# Screen.net
KiCad netlist of a schematic drawn in Altium Designer
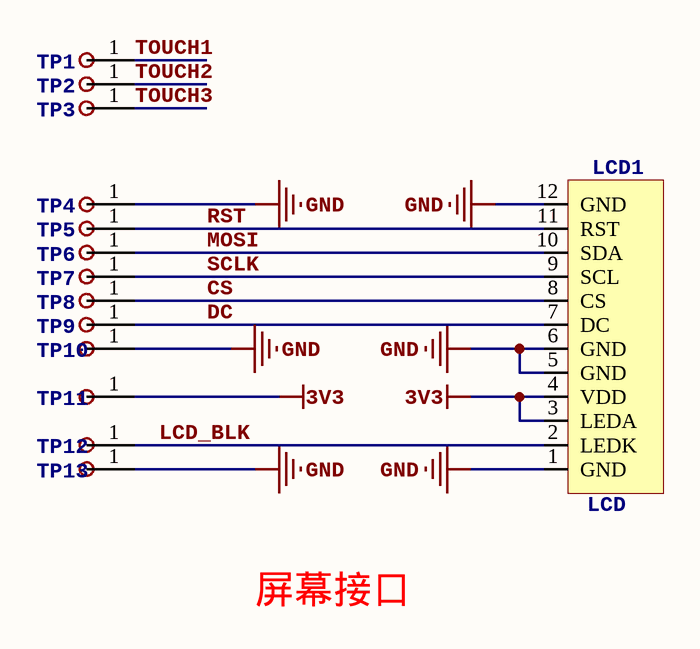
[diagram p0: Screen.SchDoc]

(export (version "E")
  (design (tool "Eeschema 10.0.6"))
  (components
    (comp (ref "LCD")
      (value "LCD1")
      (footprint "LCD-240x240-ROUND")
      (description "屏幕排线接口")
      (libsource (lib "Screen") (part "LCD"))
    )
    (comp (ref "TP1")
      (value "TP")
      (footprint "TP")
      (description "测试点")
      (libsource (lib "SuperKnob") (part "TP"))
    )
    (comp (ref "TP2")
      (value "TP")
      (footprint "TP")
      (description "测试点")
      (libsource (lib "SuperKnob") (part "TP"))
    )
    (comp (ref "TP3")
      (value "TP")
      (footprint "TP")
      (description "测试点")
      (libsource (lib "SuperKnob") (part "TP"))
    )
    (comp (ref "TP4")
      (value "TP")
      (footprint "TP")
      (description "测试点")
      (libsource (lib "SuperKnob") (part "TP"))
    )
    (comp (ref "TP5")
      (value "TP")
      (footprint "TP")
      (description "测试点")
      (libsource (lib "SuperKnob") (part "TP"))
    )
    (comp (ref "TP6")
      (value "TP")
      (footprint "TP")
      (description "测试点")
      (libsource (lib "SuperKnob") (part "TP"))
    )
    (comp (ref "TP7")
      (value "TP")
      (footprint "TP")
      (description "测试点")
      (libsource (lib "SuperKnob") (part "TP"))
    )
    (comp (ref "TP8")
      (value "TP")
      (footprint "TP")
      (description "测试点")
      (libsource (lib "SuperKnob") (part "TP"))
    )
    (comp (ref "TP9")
      (value "TP")
      (footprint "TP")
      (description "测试点")
      (libsource (lib "SuperKnob") (part "TP"))
    )
    (comp (ref "TP10")
      (value "TP")
      (footprint "TP")
      (description "测试点")
      (libsource (lib "SuperKnob") (part "TP"))
    )
    (comp (ref "TP11")
      (value "TP")
      (footprint "TP")
      (description "测试点")
      (libsource (lib "SuperKnob") (part "TP"))
    )
    (comp (ref "TP12")
      (value "TP")
      (footprint "TP")
      (description "测试点")
      (libsource (lib "SuperKnob") (part "TP"))
    )
    (comp (ref "TP13")
      (value "TP")
      (footprint "TP")
      (description "测试点")
      (libsource (lib "SuperKnob") (part "TP"))
    )
  )
  (nets
    (net (code "1") (name "/CS") (class "Default")
      (node (ref "LCD") (pin "8") (pinfunction "CS_8") (pintype "passive"))
      (node (ref "TP8") (pin "1") (pinfunction "1_1") (pintype "passive"))
    )
    (net (code "2") (name "/DC") (class "Default")
      (node (ref "LCD") (pin "7") (pinfunction "DC_7") (pintype "passive"))
      (node (ref "TP9") (pin "1") (pinfunction "1_1") (pintype "passive"))
    )
    (net (code "3") (name "/LCD_BLK") (class "Default")
      (node (ref "LCD") (pin "2") (pinfunction "LEDK_2") (pintype "passive"))
      (node (ref "TP12") (pin "1") (pinfunction "1_1") (pintype "passive"))
    )
    (net (code "4") (name "/MOSI") (class "Default")
      (node (ref "LCD") (pin "10") (pinfunction "SDA_10") (pintype "passive"))
      (node (ref "TP6") (pin "1") (pinfunction "1_1") (pintype "passive"))
    )
    (net (code "5") (name "/RST") (class "Default")
      (node (ref "LCD") (pin "11") (pinfunction "RST_11") (pintype "passive"))
      (node (ref "TP5") (pin "1") (pinfunction "1_1") (pintype "passive"))
    )
    (net (code "6") (name "/SCLK") (class "Default")
      (node (ref "LCD") (pin "9") (pinfunction "SCL_9") (pintype "passive"))
      (node (ref "TP7") (pin "1") (pinfunction "1_1") (pintype "passive"))
    )
    (net (code "7") (name "/TOUCH1") (class "Default")
      (node (ref "TP1") (pin "1") (pinfunction "1_1") (pintype "passive"))
    )
    (net (code "8") (name "/TOUCH2") (class "Default")
      (node (ref "TP2") (pin "1") (pinfunction "1_1") (pintype "passive"))
    )
    (net (code "9") (name "/TOUCH3") (class "Default")
      (node (ref "TP3") (pin "1") (pinfunction "1_1") (pintype "passive"))
    )
    (net (code "10") (name "3V3") (class "Default")
      (node (ref "LCD") (pin "3") (pinfunction "LEDA_3") (pintype "passive"))
      (node (ref "LCD") (pin "4") (pinfunction "VDD_4") (pintype "passive"))
      (node (ref "TP11") (pin "1") (pinfunction "1_1") (pintype "passive"))
    )
    (net (code "11") (name "GND") (class "Default")
      (node (ref "LCD") (pin "1") (pinfunction "GND_1") (pintype "passive"))
      (node (ref "LCD") (pin "12") (pinfunction "GND_12") (pintype "passive"))
      (node (ref "LCD") (pin "5") (pinfunction "GND_5") (pintype "passive"))
      (node (ref "LCD") (pin "6") (pinfunction "GND_6") (pintype "passive"))
      (node (ref "TP10") (pin "1") (pinfunction "1_1") (pintype "passive"))
      (node (ref "TP13") (pin "1") (pinfunction "1_1") (pintype "passive"))
      (node (ref "TP4") (pin "1") (pinfunction "1_1") (pintype "passive"))
    )
  )
)
